# SAO_3.net
KiCad netlist of a schematic drawn in EAGLE
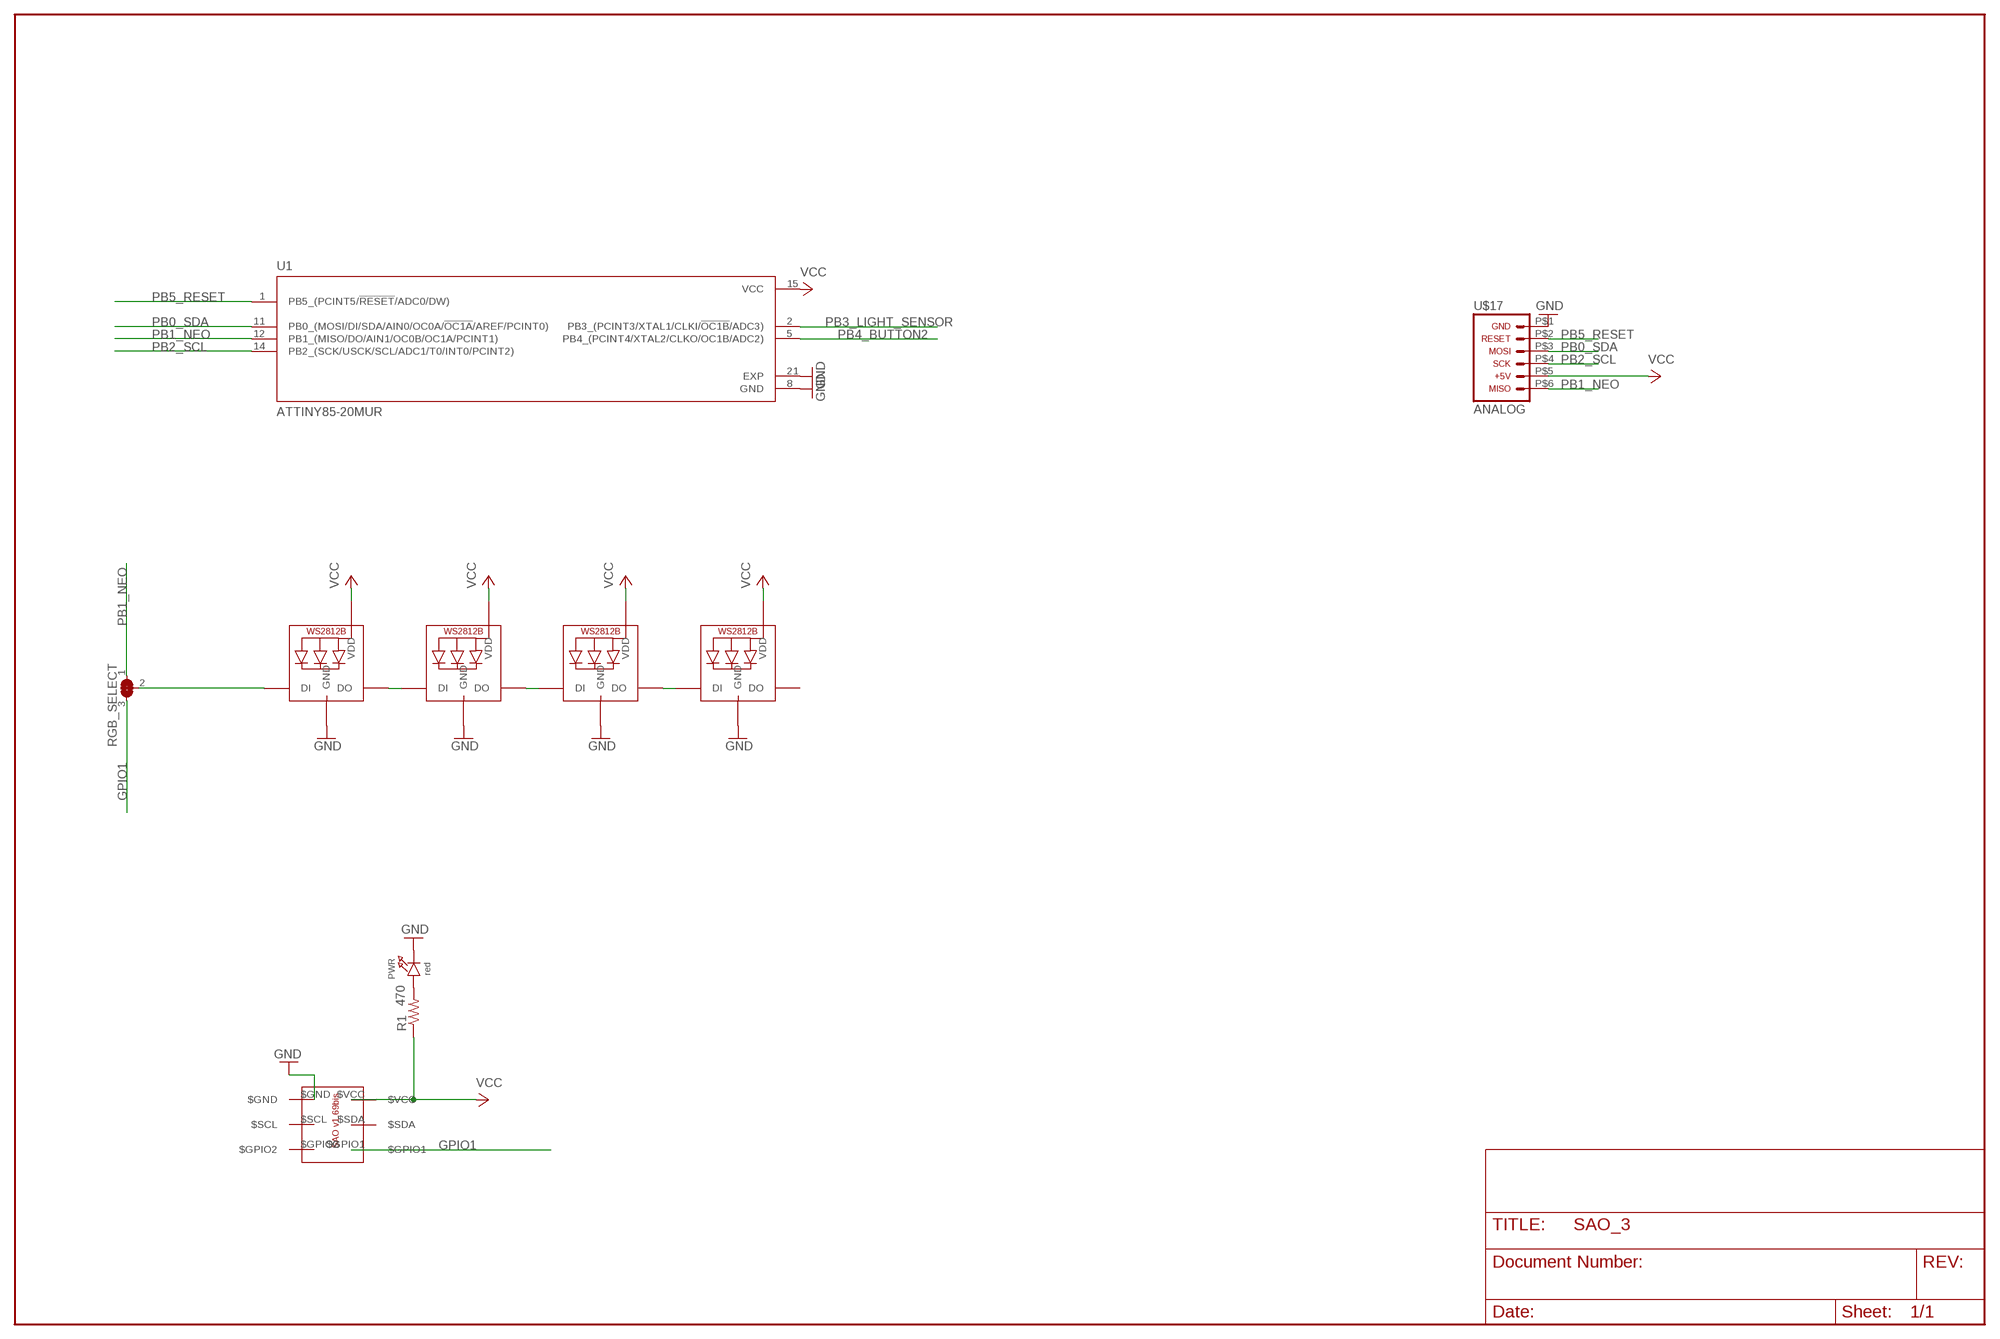
[diagram p0: schematic, sheet 1]

(export (version "E")
  (design (tool "Eeschema 10.0.6"))
  (components
    (comp (ref "LED1")
      (value "WS2812B3535")
      (footprint "eagle-import:LED3535")
      (libsource (lib "eagle-import") (part "WS2812B3535"))
    )
    (comp (ref "LED2")
      (value "WS2812B3535")
      (footprint "eagle-import:LED3535")
      (libsource (lib "eagle-import") (part "WS2812B3535"))
    )
    (comp (ref "LED3")
      (value "WS2812B3535")
      (footprint "eagle-import:LED3535")
      (libsource (lib "eagle-import") (part "WS2812B3535"))
    )
    (comp (ref "LED4")
      (value "WS2812B3535")
      (footprint "eagle-import:LED3535")
      (libsource (lib "eagle-import") (part "WS2812B3535"))
    )
    (comp (ref "PWR")
      (value "red")
      (footprint "eagle-import:CHIPLED_0805_NOOUTLINE")
      (libsource (lib "eagle-import") (part "LED0805_NOOUTLINE"))
    )
    (comp (ref "R1")
      (value "470")
      (footprint "eagle-import:R0805")
      (libsource (lib "eagle-import") (part "R-US_R0805"))
    )
    (comp (ref "RGB_SELECT")
      (value "SOLDERJUMPER_2WAY")
      (footprint "eagle-import:SOLDERJUMPER_2WAY_OPEN_NOPASTE")
      (libsource (lib "eagle-import") (part "SOLDERJUMPER_2WAY"))
    )
    (comp (ref "U$3")
      (value "SAO-1.69")
      (footprint "eagle-import:2X3-SHROUDED-FEMALE")
      (libsource (lib "eagle-import") (part "SAO-1.69"))
    )
    (comp (ref "U$17")
      (value "ICSP_FLATSMD_2X3")
      (footprint "eagle-import:CONN-SMD-2X3")
      (libsource (lib "eagle-import") (part "ICSP_FLATSMD_2X3"))
    )
    (comp (ref "U1")
      (value "ATTINY85-20MUR")
      (footprint "eagle-import:QFN50P400X400X80-21N")
      (fields (field (name "MF") "Atmel"))
      (libsource (lib "eagle-import") (part "ATTINY85-20MUR"))
    )
  )
  (nets
    (net (code "1") (name "/GPIO1") (class "Default")
      (node (ref "RGB_SELECT") (pin "3") (pinfunction "3_3") (pintype "passive"))
      (node (ref "U$3") (pin "$GPIO1") (pinfunction "$GPIO1_$GPIO1") (pintype "bidirectional"))
    )
    (net (code "2") (name "/PB0_SDA") (class "Default")
      (node (ref "U$17") (pin "P$3") (pinfunction "3_P$3") (pintype "passive"))
      (node (ref "U1") (pin "11") (pinfunction "PB0_(MOSI/DI/SDA/AIN0/OC0A/~{OC1A}/AREF/PCINT0)_11") (pintype "bidirectional"))
    )
    (net (code "3") (name "/PB1_NEO") (class "Default")
      (node (ref "RGB_SELECT") (pin "1") (pinfunction "1_1") (pintype "passive"))
      (node (ref "U$17") (pin "P$6") (pinfunction "6_P$6") (pintype "passive"))
      (node (ref "U1") (pin "12") (pinfunction "PB1_(MISO/DO/AIN1/OC0B/OC1A/PCINT1)_12") (pintype "bidirectional"))
    )
    (net (code "4") (name "/PB2_SCL") (class "Default")
      (node (ref "U$17") (pin "P$4") (pinfunction "4_P$4") (pintype "passive"))
      (node (ref "U1") (pin "14") (pinfunction "PB2_(SCK/USCK/SCL/ADC1/T0/INT0/PCINT2)_14") (pintype "bidirectional"))
    )
    (net (code "5") (name "/PB3_LIGHT_SENSOR") (class "Default")
      (node (ref "U1") (pin "2") (pinfunction "PB3_(PCINT3/XTAL1/CLKI/~{OC1B}/ADC3)_2") (pintype "bidirectional"))
    )
    (net (code "6") (name "/PB4_BUTTON2") (class "Default")
      (node (ref "U1") (pin "5") (pinfunction "PB4_(PCINT4/XTAL2/CLKO/OC1B/ADC2)_5") (pintype "bidirectional"))
    )
    (net (code "7") (name "/PB5_RESET") (class "Default")
      (node (ref "U$17") (pin "P$2") (pinfunction "2_P$2") (pintype "passive"))
      (node (ref "U1") (pin "1") (pinfunction "PB5_(PCINT5/~{RESET}/ADC0/DW)_1") (pintype "bidirectional"))
    )
    (net (code "8") (name "GND") (class "Default")
      (node (ref "LED1") (pin "1") (pinfunction "GND_1") (pintype "power_in"))
      (node (ref "LED2") (pin "1") (pinfunction "GND_1") (pintype "power_in"))
      (node (ref "LED3") (pin "1") (pinfunction "GND_1") (pintype "power_in"))
      (node (ref "LED4") (pin "1") (pinfunction "GND_1") (pintype "power_in"))
      (node (ref "PWR") (pin "C") (pinfunction "C_C") (pintype "passive"))
      (node (ref "U$17") (pin "P$1") (pinfunction "1_P$1") (pintype "passive"))
      (node (ref "U$3") (pin "$GND") (pinfunction "$GND_$GND") (pintype "bidirectional"))
      (node (ref "U1") (pin "21") (pinfunction "EXP_21") (pintype "power_in"))
      (node (ref "U1") (pin "8") (pinfunction "GND_8") (pintype "power_in"))
    )
    (net (code "9") (name "Net-(LED1-DI)") (class "Default")
      (node (ref "LED1") (pin "2") (pinfunction "DI_2") (pintype "input"))
      (node (ref "RGB_SELECT") (pin "2") (pinfunction "2_2") (pintype "passive"))
    )
    (net (code "10") (name "Net-(LED1-DO)") (class "Default")
      (node (ref "LED1") (pin "4") (pinfunction "DO_4") (pintype "output"))
      (node (ref "LED2") (pin "2") (pinfunction "DI_2") (pintype "input"))
    )
    (net (code "11") (name "Net-(LED2-DO)") (class "Default")
      (node (ref "LED2") (pin "4") (pinfunction "DO_4") (pintype "output"))
      (node (ref "LED3") (pin "2") (pinfunction "DI_2") (pintype "input"))
    )
    (net (code "12") (name "Net-(LED3-DO)") (class "Default")
      (node (ref "LED3") (pin "4") (pinfunction "DO_4") (pintype "output"))
      (node (ref "LED4") (pin "2") (pinfunction "DI_2") (pintype "input"))
    )
    (net (code "13") (name "Net-(PWR-PadA)") (class "Default")
      (node (ref "PWR") (pin "A") (pinfunction "A_A") (pintype "passive"))
      (node (ref "R1") (pin "2") (pinfunction "2_2") (pintype "passive"))
    )
    (net (code "14") (name "VCC") (class "Default")
      (node (ref "LED1") (pin "3") (pinfunction "VDD_3") (pintype "power_in"))
      (node (ref "LED2") (pin "3") (pinfunction "VDD_3") (pintype "power_in"))
      (node (ref "LED3") (pin "3") (pinfunction "VDD_3") (pintype "power_in"))
      (node (ref "LED4") (pin "3") (pinfunction "VDD_3") (pintype "power_in"))
      (node (ref "R1") (pin "1") (pinfunction "1_1") (pintype "passive"))
      (node (ref "U$17") (pin "P$5") (pinfunction "5_P$5") (pintype "passive"))
      (node (ref "U$3") (pin "$VCC") (pinfunction "$VCC_$VCC") (pintype "bidirectional"))
      (node (ref "U1") (pin "15") (pinfunction "VCC_15") (pintype "power_in"))
    )
    (net (code "15") (name "unconnected-(LED4-DO-Pad4)") (class "Default")
      (node (ref "LED4") (pin "4") (pinfunction "DO_4") (pintype "output"))
    )
    (net (code "16") (name "unconnected-(U$3-Pad$GPIO2)") (class "Default")
      (node (ref "U$3") (pin "$GPIO2") (pinfunction "$GPIO2_$GPIO2") (pintype "bidirectional"))
    )
    (net (code "17") (name "unconnected-(U$3-Pad$SCL)") (class "Default")
      (node (ref "U$3") (pin "$SCL") (pinfunction "$SCL_$SCL") (pintype "bidirectional"))
    )
    (net (code "18") (name "unconnected-(U$3-Pad$SDA)") (class "Default")
      (node (ref "U$3") (pin "$SDA") (pinfunction "$SDA_$SDA") (pintype "bidirectional"))
    )
  )
)
